# SolarCharger.net
KiCad netlist of a schematic drawn in Altium Designer
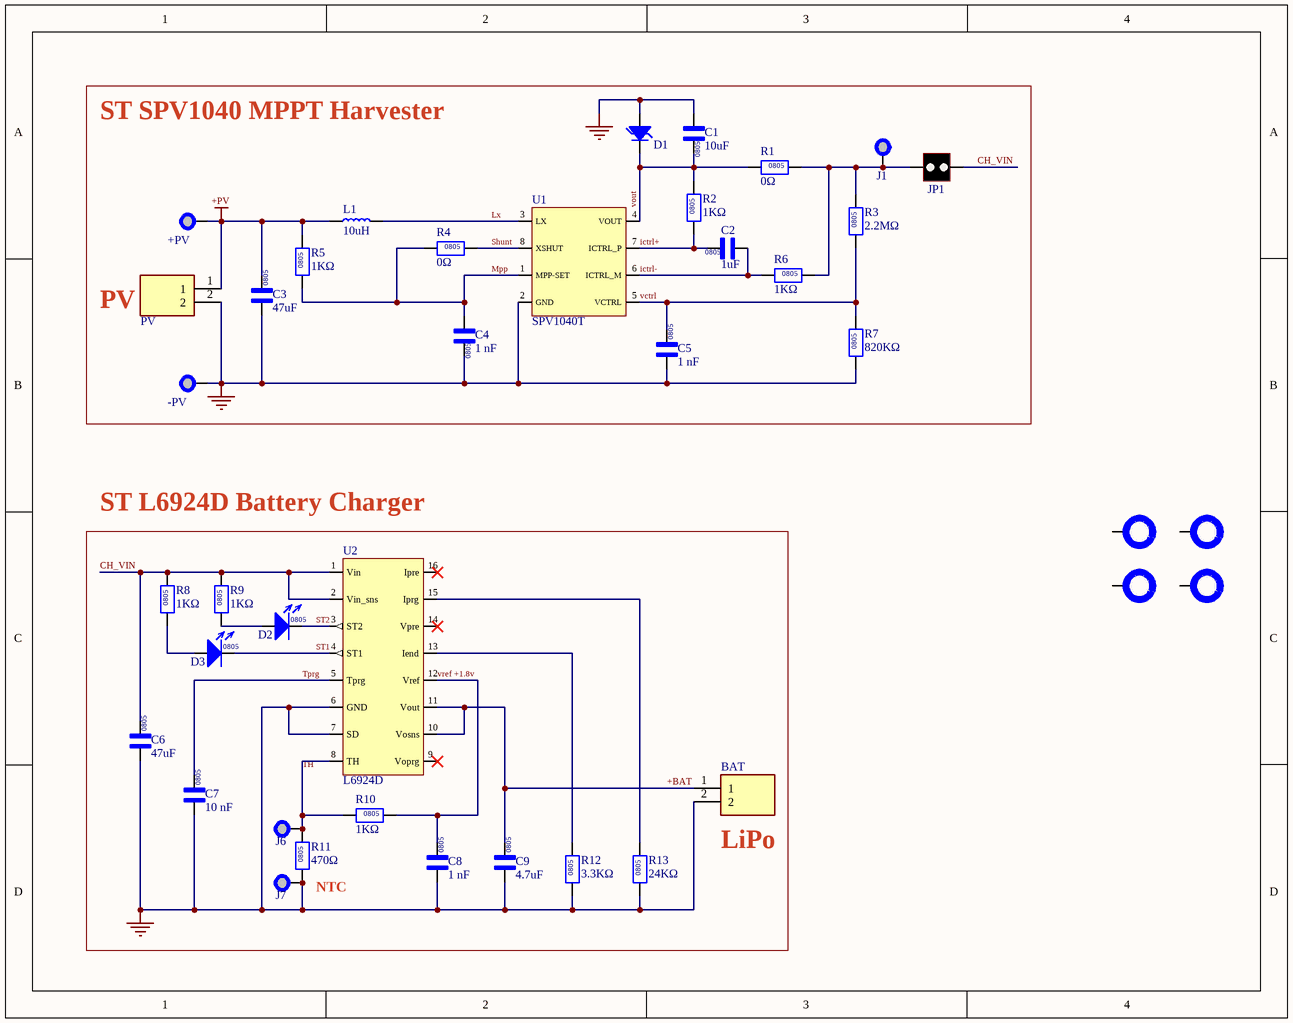
[diagram p0: SolarCharger.SchDoc]

(export (version "E")
  (design (tool "Eeschema 10.0.6"))
  (components
    (comp (ref "+PV")
      (value "Power Pad")
      (footprint "PAD")
      (description "Power pad 4mmx1.5mm")
      (libsource (lib "SolarCharger") (part "PAD"))
    )
    (comp (ref "-PV")
      (value "Power Pad")
      (footprint "PAD")
      (description "Power pad 4mmx1.5mm")
      (libsource (lib "SolarCharger") (part "PAD"))
    )
    (comp (ref "BAT")
      (value "640456-2")
      (footprint "TE_640456-2")
      (description "1x2P 1 2.54mm 2 Copper Alloy Plugin,P=2.54mm Wire To Board / Wire To Wire Connector")
      (fields (field (name "MANUFACTURER") "TE"))
      (libsource (lib "") (part "640456-2_1"))
    )
    (comp (ref "C1")
      (value "10uF")
      (footprint "YAGEO-0805-C-L")
      (description "10 uF, 16 V, ± 10%, X5R, 0805")
      (fields
        (field (name "MANUFACTURER") "Yageo")
        (field (name "MANUFACTURER PART NUMBER") "CC0805KKX5R7BB106")
        (field (name "FORM") "0805")
      )
      (libsource (lib "SolarCharger") (part "CC0805KKX5R7BB106"))
    )
    (comp (ref "C2")
      (value "1uF")
      (footprint "YAGEO-0805-C-L")
      (description "1 uF, 10 V, ± 10%, X7R, 0805")
      (fields
        (field (name "MANUFACTURER") "Yageo")
        (field (name "MANUFACTURER PART NUMBER") "CC0805KKX7R6BB105")
        (field (name "FORM") "0805")
      )
      (libsource (lib "SolarCharger") (part "CC0805KKX7R6BB105"))
    )
    (comp (ref "C3")
      (value "47uF")
      (footprint "YAGEO-0805-C-L")
      (description "47 uF, 6.3 V, ± 20%, X5R, 0805")
      (fields
        (field (name "MANUFACTURER") "Samsung")
        (field (name "MANUFACTURER PART NUMBER") "CL21A476MQYNNNE")
        (field (name "FORM") "0805")
      )
      (libsource (lib "SolarCharger") (part "CL21A476MQYNNNE"))
    )
    (comp (ref "C4")
      (value "1 nF")
      (footprint "YAGEO-0805-C-L")
      (description "1 nF,  50V, 10%, X7R, 0805")
      (fields
        (field (name "MANUFACTURER") "Yageo")
        (field (name "MANUFACTURER PART NUMBER") "CC0805KRX7R9BB102")
        (field (name "FORM") "0805")
      )
      (libsource (lib "SolarCharger") (part "CC0805KRX7R9BB102"))
    )
    (comp (ref "C5")
      (value "1 nF")
      (footprint "YAGEO-0805-C-L")
      (description "1 nF,  50V, 10%, X7R, 0805")
      (fields
        (field (name "MANUFACTURER") "Yageo")
        (field (name "MANUFACTURER PART NUMBER") "CC0805KRX7R9BB102")
        (field (name "FORM") "0805")
      )
      (libsource (lib "SolarCharger") (part "CC0805KRX7R9BB102"))
    )
    (comp (ref "C6")
      (value "47uF")
      (footprint "YAGEO-0805-C-L")
      (description "47 uF, 6.3 V, ± 20%, X5R, 0805")
      (fields
        (field (name "MANUFACTURER") "Samsung")
        (field (name "MANUFACTURER PART NUMBER") "CL21A476MQYNNNE")
        (field (name "FORM") "0805")
      )
      (libsource (lib "SolarCharger") (part "CL21A476MQYNNNE"))
    )
    (comp (ref "C7")
      (value "10 nF")
      (footprint "YAGEO-0805-C-L")
      (description "10 nF, 50 V, ± 10%, X7R, 0805")
      (fields
        (field (name "MANUFACTURER") "Yageo")
        (field (name "MANUFACTURER PART NUMBER") "CC0805KRX7R9BB103")
        (field (name "FORM") "0805")
      )
      (libsource (lib "SolarCharger") (part "CC0805KRX7R9BB103"))
    )
    (comp (ref "C8")
      (value "1 nF")
      (footprint "YAGEO-0805-C-L")
      (description "1 nF,  50V, 10%, X7R, 0805")
      (fields
        (field (name "MANUFACTURER") "Yageo")
        (field (name "MANUFACTURER PART NUMBER") "CC0805KRX7R9BB102")
        (field (name "FORM") "0805")
      )
      (libsource (lib "SolarCharger") (part "CC0805KRX7R9BB102"))
    )
    (comp (ref "C9")
      (value "4.7uF")
      (footprint "YAGEO-0805-C-L")
      (description "4.7 uF, 50 V, ± 10%, X5R, 0805")
      (fields
        (field (name "MANUFACTURER") "Yageo")
        (field (name "MANUFACTURER PART NUMBER") "CC0805KKX5R8BB475")
        (field (name "FORM") "0805")
      )
      (libsource (lib "SolarCharger") (part "CC0805KKX5R8BB475"))
    )
    (comp (ref "D1")
      (value "TVS-MSKSEMI")
      (footprint "MSKSEMI-TVS-L")
      (description "TVS 9.2V 6.4V 5V SMA")
      (fields (field (name "MANUFACTURER") "MSKSEMI") (field (name "MANUFACTURER PART NUMBER") "SMAJ5.0A"))
      (libsource (lib "SolarCharger") (part "SMAJ5.0A"))
    )
    (comp (ref "D2")
      (value "SMD LED")
      (footprint "SMD-LED-L")
      (description "516nm~525nm -30℃~+85℃ Positive post Emerald 120° 80mW 0805")
      (fields
        (field (name "MANUFACTURER") "XINGLIGHT")
        (field (name "MANUFACTURER PART NUMBER") "XL-2012UGC")
        (field (name "FORM") "0805")
      )
      (libsource (lib "SolarCharger") (part "SMD LED"))
    )
    (comp (ref "D3")
      (value "SMD LED")
      (footprint "SMD-LED-L")
      (description "516nm~525nm -30℃~+85℃ Positive post Emerald 120° 80mW 0805")
      (fields
        (field (name "MANUFACTURER") "XINGLIGHT")
        (field (name "MANUFACTURER PART NUMBER") "XL-2012UGC")
        (field (name "FORM") "0805")
      )
      (libsource (lib "SolarCharger") (part "SMD LED"))
    )
    (comp (ref "J1")
      (value "Power Pad")
      (footprint "PAD")
      (description "Power pad 4mmx1.5mm")
      (libsource (lib "SolarCharger") (part "PAD"))
    )
    (comp (ref "J6")
      (value "Power Pad")
      (footprint "PAD")
      (description "Power pad 4mmx1.5mm")
      (libsource (lib "SolarCharger") (part "PAD"))
    )
    (comp (ref "J7")
      (value "Power Pad")
      (footprint "PAD")
      (description "Power pad 4mmx1.5mm")
      (libsource (lib "SolarCharger") (part "PAD"))
    )
    (comp (ref "JP1")
      (value "J2P")
      (footprint "DIP2")
      (fields (field (name "MANUFACTURER") "Liasheng") (field (name "MANUFACTURER PART NUMBER") "PH-00218"))
      (libsource (lib "SolarCharger") (part "PH-00218"))
    )
    (comp (ref "L1")
      (value "10uH")
      (footprint "Bead 10uH")
      (description "10 uH Power Inductor 20% 100KHz Ferrite 2.5A 0.061Ohm")
      (fields (field (name "MANUFACTURER") "TDK") (field (name "MANUFACTURER PART NUMBER") "VLS5045EX-100M"))
      (libsource (lib "SolarCharger") (part "VLS5045EX-100M"))
    )
    (comp (ref "MH1")
      (value "Mounting Hole")
      (footprint "Mounting Hole")
      (description "Mounting hole 7.4mm x 3.2mm")
      (libsource (lib "SolarCharger") (part "Mounting Hole"))
    )
    (comp (ref "MH2")
      (value "Mounting Hole")
      (footprint "Mounting Hole")
      (description "Mounting hole 7.4mm x 3.2mm")
      (libsource (lib "SolarCharger") (part "Mounting Hole"))
    )
    (comp (ref "MH3")
      (value "Mounting Hole")
      (footprint "Mounting Hole")
      (description "Mounting hole 7.4mm x 3.2mm")
      (libsource (lib "SolarCharger") (part "Mounting Hole"))
    )
    (comp (ref "MH4")
      (value "Mounting Hole")
      (footprint "Mounting Hole")
      (description "Mounting hole 7.4mm x 3.2mm")
      (libsource (lib "SolarCharger") (part "Mounting Hole"))
    )
    (comp (ref "PV")
      (value "640456-2")
      (footprint "TE_640456-2")
      (description "1x2P 1 2.54mm 2 Copper Alloy Plugin,P=2.54mm Wire To Board / Wire To Wire Connector")
      (fields (field (name "MANUFACTURER") "TE"))
      (libsource (lib "SolarCharger") (part "640456-2"))
    )
    (comp (ref "R1")
      (value "0Ω")
      (footprint "YAGEO-0805-R-L")
      (description "0 Ohm, 1%, 0.125W, 0805")
      (fields
        (field (name "MANUFACTURER") "Yageo")
        (field (name "MANUFACTURER PART NUMBER") "AC0805FR-070RL")
        (field (name "FORM") "0805")
      )
      (libsource (lib "SolarCharger") (part "AC0805FR-070RL"))
    )
    (comp (ref "R2")
      (value "1KΩ")
      (footprint "YAGEO-0805-R-L")
      (description "1 kOhm, ± 1%, 125 mW, 0805")
      (fields
        (field (name "MANUFACTURER") "Yageo")
        (field (name "MANUFACTURER PART NUMBER") "RC0805FR-071KL")
        (field (name "FORM") "0805")
      )
      (libsource (lib "SolarCharger") (part "RC0805FR-071KL"))
    )
    (comp (ref "R3")
      (value "2.2MΩ")
      (footprint "YAGEO-0805-R-L")
      (description "2.2 MOhm, ± 1%, 125 mW, 0805")
      (fields
        (field (name "MANUFACTURER") "Yageo")
        (field (name "MANUFACTURER PART NUMBER") "RC0805FR-072M2L")
        (field (name "FORM") "0805")
      )
      (libsource (lib "SolarCharger") (part "RC0805FR-072M2L"))
    )
    (comp (ref "R4")
      (value "0Ω")
      (footprint "YAGEO-0805-R-L")
      (description "0 Ohm, 1%, 0.125W, 0805")
      (fields
        (field (name "MANUFACTURER") "Yageo")
        (field (name "MANUFACTURER PART NUMBER") "AC0805FR-070RL")
        (field (name "FORM") "0805")
      )
      (libsource (lib "SolarCharger") (part "AC0805FR-070RL"))
    )
    (comp (ref "R5")
      (value "1KΩ")
      (footprint "YAGEO-0805-R-L")
      (description "1 kOhm, ± 1%, 125 mW, 0805")
      (fields
        (field (name "MANUFACTURER") "Yageo")
        (field (name "MANUFACTURER PART NUMBER") "RC0805FR-071KL")
        (field (name "FORM") "0805")
      )
      (libsource (lib "SolarCharger") (part "RC0805FR-071KL"))
    )
    (comp (ref "R6")
      (value "1KΩ")
      (footprint "YAGEO-0805-R-L")
      (description "1 kOhm, ± 1%, 125 mW, 0805")
      (fields
        (field (name "MANUFACTURER") "Yageo")
        (field (name "MANUFACTURER PART NUMBER") "RC0805FR-071KL")
        (field (name "FORM") "0805")
      )
      (libsource (lib "SolarCharger") (part "RC0805FR-071KL"))
    )
    (comp (ref "R7")
      (value "820KΩ")
      (footprint "YAGEO-0805-R-L")
      (description "820 kOhm, ± 1%, 125 mW, 0805")
      (fields
        (field (name "MANUFACTURER") "Yageo")
        (field (name "MANUFACTURER PART NUMBER") "RC0805FR-07820KL")
        (field (name "FORM") "0805")
      )
      (libsource (lib "SolarCharger") (part "RC0805FR-07820KL"))
    )
    (comp (ref "R8")
      (value "1KΩ")
      (footprint "YAGEO-0805-R-L")
      (description "1 kOhm, ± 1%, 125 mW, 0805")
      (fields
        (field (name "MANUFACTURER") "Yageo")
        (field (name "MANUFACTURER PART NUMBER") "RC0805FR-071KL")
        (field (name "FORM") "0805")
      )
      (libsource (lib "SolarCharger") (part "RC0805FR-071KL"))
    )
    (comp (ref "R9")
      (value "1KΩ")
      (footprint "YAGEO-0805-R-L")
      (description "1 kOhm, ± 1%, 125 mW, 0805")
      (fields
        (field (name "MANUFACTURER") "Yageo")
        (field (name "MANUFACTURER PART NUMBER") "RC0805FR-071KL")
        (field (name "FORM") "0805")
      )
      (libsource (lib "SolarCharger") (part "RC0805FR-071KL"))
    )
    (comp (ref "R10")
      (value "1KΩ")
      (footprint "YAGEO-0805-R-L")
      (description "1 kOhm, ± 1%, 125 mW, 0805")
      (fields
        (field (name "MANUFACTURER") "Yageo")
        (field (name "MANUFACTURER PART NUMBER") "RC0805FR-071KL")
        (field (name "FORM") "0805")
      )
      (libsource (lib "SolarCharger") (part "RC0805FR-071KL"))
    )
    (comp (ref "R11")
      (value "470Ω")
      (footprint "YAGEO-0805-R-L")
      (description "470 Ohm, ± 1%, 125 mW, 0805")
      (fields
        (field (name "MANUFACTURER") "Yageo")
        (field (name "MANUFACTURER PART NUMBER") "RC0805FR-07470RL")
        (field (name "FORM") "0805")
      )
      (libsource (lib "SolarCharger") (part "RC0805FR-07470RL"))
    )
    (comp (ref "R12")
      (value "3.3KΩ")
      (footprint "YAGEO-0805-R-L")
      (description "3.3 kOhm, ± 1%, 125 mW, 0805")
      (fields
        (field (name "MANUFACTURER") "Yageo")
        (field (name "MANUFACTURER PART NUMBER") "RC0805FR-073K3L")
        (field (name "FORM") "0805")
      )
      (libsource (lib "SolarCharger") (part "RC0805FR-073K3L"))
    )
    (comp (ref "R13")
      (value "24KΩ")
      (footprint "YAGEO-0805-R-L")
      (description "24 kOhm, ± 1%, 125 mW, 0805")
      (fields
        (field (name "MANUFACTURER") "Yageo")
        (field (name "MANUFACTURER PART NUMBER") "RC0805FR-0724KL")
        (field (name "FORM") "0805")
      )
      (libsource (lib "SolarCharger") (part "RC0805FR-0724KL"))
    )
    (comp (ref "U1")
      (value "SPV1040T")
      (footprint "SOP65P640X120-8N")
      (description "IC BATTERY CHARGER SOLAR 8TSSOP")
      (fields (field (name "MANUFACTURER") "STMicroelectronics"))
      (libsource (lib "SolarCharger") (part "SPV1040T"))
    )
    (comp (ref "U2")
      (value "L6924D")
      (footprint "QFN50P300X300X100-17L-D")
      (description "Battery Charger Li-Ion/Li-Pol 30mA 4.1V 16-Pin VFQFPN EP")
      (fields (field (name "MANUFACTURER") "STMicroelectronics"))
      (libsource (lib "SolarCharger") (part "L6924D"))
    )
  )
  (nets
    (net (code "1") (name "+PV") (class "Default")
      (node (ref "+PV") (pin "1") (pinfunction "1_1") (pintype "passive"))
      (node (ref "C3") (pin "1") (pinfunction "1_1") (pintype "passive"))
      (node (ref "L1") (pin "1") (pinfunction "1_1") (pintype "passive"))
      (node (ref "PV") (pin "1") (pinfunction "1_1") (pintype "passive"))
      (node (ref "R5") (pin "2") (pinfunction "2_2") (pintype "passive"))
    )
    (net (code "2") (name "/+BAT") (class "Default")
      (node (ref "BAT") (pin "1") (pinfunction "1_1") (pintype "passive"))
      (node (ref "C9") (pin "1") (pinfunction "1_1") (pintype "passive"))
      (node (ref "U2") (pin "10") (pinfunction "Vosns_10") (pintype "passive"))
      (node (ref "U2") (pin "11") (pinfunction "Vout_11") (pintype "passive"))
    )
    (net (code "3") (name "/CH_VIN") (class "Default")
      (node (ref "C6") (pin "1") (pinfunction "1_1") (pintype "passive"))
      (node (ref "JP1") (pin "2") (pinfunction "2_2") (pintype "passive"))
      (node (ref "R8") (pin "2") (pinfunction "2_2") (pintype "passive"))
      (node (ref "R9") (pin "2") (pinfunction "2_2") (pintype "passive"))
      (node (ref "U2") (pin "1") (pinfunction "Vin_1") (pintype "passive"))
      (node (ref "U2") (pin "2") (pinfunction "Vin_sns_2") (pintype "passive"))
    )
    (net (code "4") (name "/Lx") (class "Default")
      (node (ref "L1") (pin "2") (pinfunction "2_2") (pintype "passive"))
      (node (ref "U1") (pin "3") (pinfunction "LX_3") (pintype "power_in"))
    )
    (net (code "5") (name "/Mpp") (class "Default")
      (node (ref "C4") (pin "1") (pinfunction "1_1") (pintype "passive"))
      (node (ref "R4") (pin "1") (pinfunction "1_1") (pintype "passive"))
      (node (ref "R5") (pin "1") (pinfunction "1_1") (pintype "passive"))
      (node (ref "U1") (pin "1") (pinfunction "MPP-SET_1") (pintype "power_in"))
    )
    (net (code "6") (name "/ST1") (class "Default")
      (node (ref "D3") (pin "2") (pinfunction "2_2") (pintype "passive"))
      (node (ref "U2") (pin "4") (pinfunction "ST1_4") (pintype "output"))
    )
    (net (code "7") (name "/ST2") (class "Default")
      (node (ref "D2") (pin "2") (pinfunction "2_2") (pintype "passive"))
      (node (ref "U2") (pin "3") (pinfunction "ST2_3") (pintype "output"))
    )
    (net (code "8") (name "/Shunt") (class "Default")
      (node (ref "R4") (pin "2") (pinfunction "2_2") (pintype "passive"))
      (node (ref "U1") (pin "8") (pinfunction "XSHUT_8") (pintype "power_in"))
    )
    (net (code "9") (name "/TH") (class "Default")
      (node (ref "J6") (pin "1") (pinfunction "1_1") (pintype "passive"))
      (node (ref "R10") (pin "1") (pinfunction "1_1") (pintype "passive"))
      (node (ref "R11") (pin "2") (pinfunction "2_2") (pintype "passive"))
      (node (ref "U2") (pin "8") (pinfunction "TH_8") (pintype "passive"))
    )
    (net (code "10") (name "/Tprg") (class "Default")
      (node (ref "C7") (pin "1") (pinfunction "1_1") (pintype "passive"))
      (node (ref "U2") (pin "5") (pinfunction "Tprg_5") (pintype "passive"))
    )
    (net (code "11") (name "/ictrl+") (class "Default")
      (node (ref "C2") (pin "2") (pinfunction "2_2") (pintype "passive"))
      (node (ref "R2") (pin "1") (pinfunction "1_1") (pintype "passive"))
      (node (ref "U1") (pin "7") (pinfunction "ICTRL_P_7") (pintype "power_in"))
    )
    (net (code "12") (name "/ictrl-") (class "Default")
      (node (ref "C2") (pin "1") (pinfunction "1_1") (pintype "passive"))
      (node (ref "R6") (pin "1") (pinfunction "1_1") (pintype "passive"))
      (node (ref "U1") (pin "6") (pinfunction "ICTRL_M_6") (pintype "power_in"))
    )
    (net (code "13") (name "/vctrl") (class "Default")
      (node (ref "C5") (pin "1") (pinfunction "1_1") (pintype "passive"))
      (node (ref "R3") (pin "1") (pinfunction "1_1") (pintype "passive"))
      (node (ref "R7") (pin "2") (pinfunction "2_2") (pintype "passive"))
      (node (ref "U1") (pin "5") (pinfunction "VCTRL_5") (pintype "power_in"))
    )
    (net (code "14") (name "/vout") (class "Default")
      (node (ref "C1") (pin "2") (pinfunction "2_2") (pintype "passive"))
      (node (ref "D1") (pin "1") (pinfunction "1_1") (pintype "passive"))
      (node (ref "R1") (pin "1") (pinfunction "1_1") (pintype "passive"))
      (node (ref "R2") (pin "2") (pinfunction "2_2") (pintype "passive"))
      (node (ref "U1") (pin "4") (pinfunction "VOUT_4") (pintype "power_in"))
    )
    (net (code "15") (name "/vref +1.8v") (class "Default")
      (node (ref "C8") (pin "1") (pinfunction "1_1") (pintype "passive"))
      (node (ref "R10") (pin "2") (pinfunction "2_2") (pintype "passive"))
      (node (ref "U2") (pin "12") (pinfunction "Vref_12") (pintype "passive"))
    )
    (net (code "16") (name "GND") (class "Default")
      (node (ref "-PV") (pin "1") (pinfunction "1_1") (pintype "passive"))
      (node (ref "BAT") (pin "2") (pinfunction "2_2") (pintype "passive"))
      (node (ref "C1") (pin "1") (pinfunction "1_1") (pintype "passive"))
      (node (ref "C3") (pin "2") (pinfunction "2_2") (pintype "passive"))
      (node (ref "C4") (pin "2") (pinfunction "2_2") (pintype "passive"))
      (node (ref "C5") (pin "2") (pinfunction "2_2") (pintype "passive"))
      (node (ref "C6") (pin "2") (pinfunction "2_2") (pintype "passive"))
      (node (ref "C7") (pin "2") (pinfunction "2_2") (pintype "passive"))
      (node (ref "C8") (pin "2") (pinfunction "2_2") (pintype "passive"))
      (node (ref "C9") (pin "2") (pinfunction "2_2") (pintype "passive"))
      (node (ref "D1") (pin "2") (pinfunction "2_2") (pintype "passive"))
      (node (ref "J7") (pin "1") (pinfunction "1_1") (pintype "passive"))
      (node (ref "PV") (pin "2") (pinfunction "2_2") (pintype "passive"))
      (node (ref "R11") (pin "1") (pinfunction "1_1") (pintype "passive"))
      (node (ref "R12") (pin "1") (pinfunction "1_1") (pintype "passive"))
      (node (ref "R13") (pin "1") (pinfunction "1_1") (pintype "passive"))
      (node (ref "R7") (pin "1") (pinfunction "1_1") (pintype "passive"))
      (node (ref "U1") (pin "2") (pinfunction "GND_2") (pintype "passive"))
      (node (ref "U2") (pin "6") (pinfunction "GND_6") (pintype "passive"))
      (node (ref "U2") (pin "7") (pinfunction "SD_7") (pintype "passive"))
    )
    (net (code "17") (name "Net-(D2-Pad1)") (class "Default")
      (node (ref "D2") (pin "1") (pinfunction "1_1") (pintype "passive"))
      (node (ref "R9") (pin "1") (pinfunction "1_1") (pintype "passive"))
    )
    (net (code "18") (name "Net-(D3-Pad1)") (class "Default")
      (node (ref "D3") (pin "1") (pinfunction "1_1") (pintype "passive"))
      (node (ref "R8") (pin "1") (pinfunction "1_1") (pintype "passive"))
    )
    (net (code "19") (name "Net-(J1-Pad1)") (class "Default")
      (node (ref "J1") (pin "1") (pinfunction "1_1") (pintype "passive"))
      (node (ref "JP1") (pin "1") (pinfunction "1_1") (pintype "passive"))
      (node (ref "R1") (pin "2") (pinfunction "2_2") (pintype "passive"))
      (node (ref "R3") (pin "2") (pinfunction "2_2") (pintype "passive"))
      (node (ref "R6") (pin "2") (pinfunction "2_2") (pintype "passive"))
    )
    (net (code "20") (name "Net-(U2-Iend)") (class "Default")
      (node (ref "R12") (pin "2") (pinfunction "2_2") (pintype "passive"))
      (node (ref "U2") (pin "13") (pinfunction "Iend_13") (pintype "passive"))
    )
    (net (code "21") (name "Net-(U2-Iprg)") (class "Default")
      (node (ref "R13") (pin "2") (pinfunction "2_2") (pintype "passive"))
      (node (ref "U2") (pin "15") (pinfunction "Iprg_15") (pintype "passive"))
    )
    (net (code "22") (name "unconnected-(MH1-Pad1)") (class "Default")
      (node (ref "MH1") (pin "1") (pinfunction "1_1") (pintype "passive"))
    )
    (net (code "23") (name "unconnected-(MH2-Pad1)") (class "Default")
      (node (ref "MH2") (pin "1") (pinfunction "1_1") (pintype "passive"))
    )
    (net (code "24") (name "unconnected-(MH3-Pad1)") (class "Default")
      (node (ref "MH3") (pin "1") (pinfunction "1_1") (pintype "passive"))
    )
    (net (code "25") (name "unconnected-(MH4-Pad1)") (class "Default")
      (node (ref "MH4") (pin "1") (pinfunction "1_1") (pintype "passive"))
    )
    (net (code "26") (name "unconnected-(U2-Ipre-Pad16)") (class "Default")
      (node (ref "U2") (pin "16") (pinfunction "Ipre_16") (pintype "passive+no_connect"))
    )
    (net (code "27") (name "unconnected-(U2-Voprg-Pad9)") (class "Default")
      (node (ref "U2") (pin "9") (pinfunction "Voprg_9") (pintype "passive+no_connect"))
    )
    (net (code "28") (name "unconnected-(U2-Vpre-Pad14)") (class "Default")
      (node (ref "U2") (pin "14") (pinfunction "Vpre_14") (pintype "passive+no_connect"))
    )
  )
)
